# BSPD_5_11_27.net
KiCad netlist of a schematic drawn in EAGLE
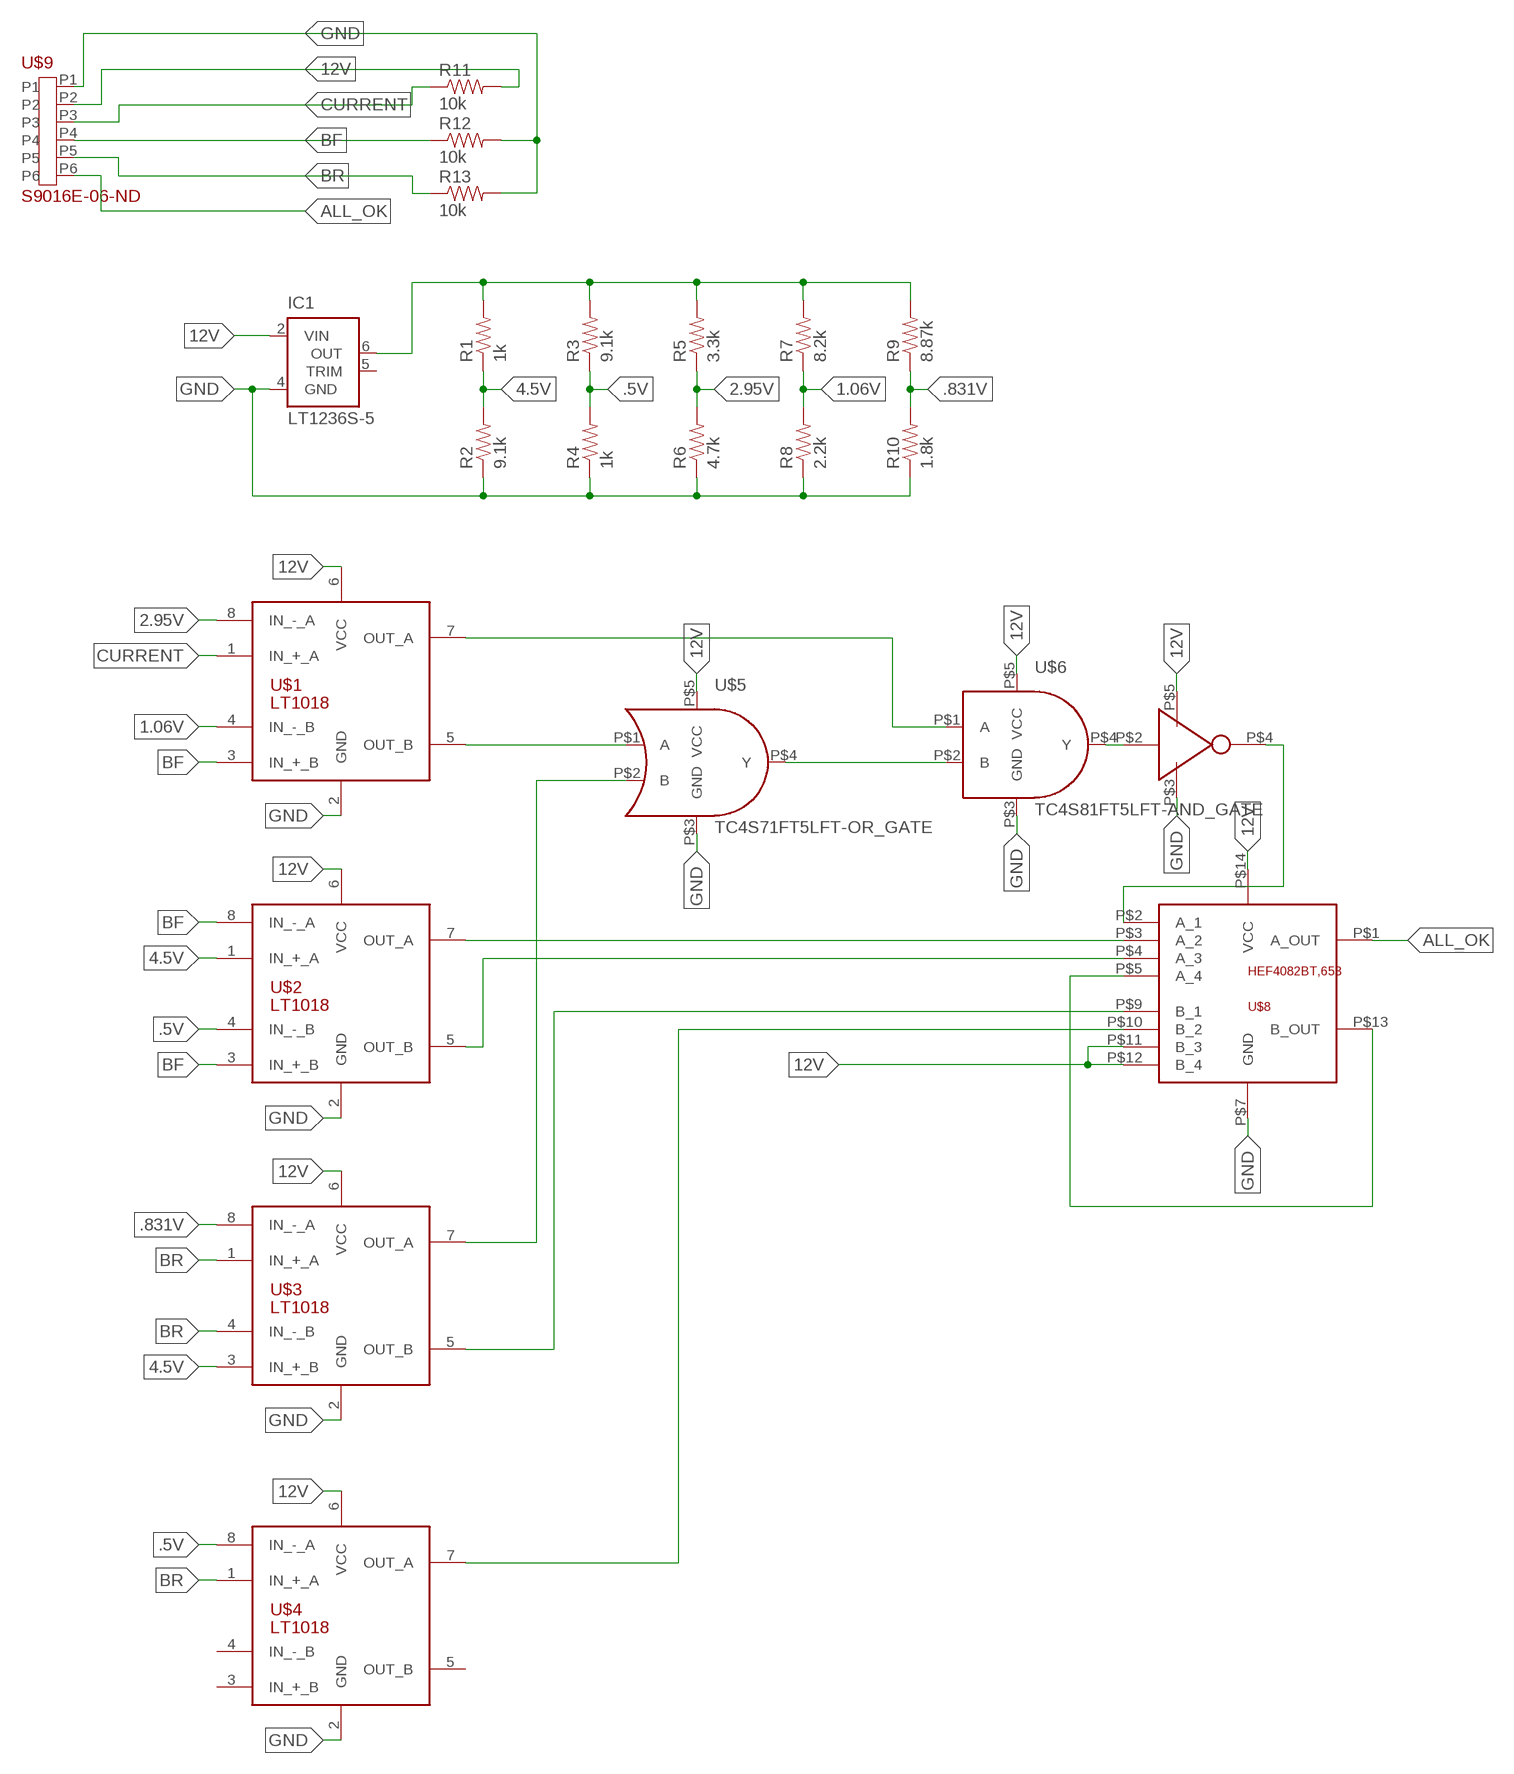
[diagram p0: schematic, sheet 1]

(export (version "E")
  (design (tool "Eeschema 10.0.6"))
  (components
    (comp (ref "IC1")
      (value "LT1236S-5")
      (footprint "eagle-import:SOIC8")
      (libsource (lib "eagle-import") (part "LT1236?S-5"))
    )
    (comp (ref "R1")
      (value "1k")
      (footprint "eagle-import:0603-RES")
      (libsource (lib "eagle-import") (part "RESISTOR0603"))
    )
    (comp (ref "R2")
      (value "9.1k")
      (footprint "eagle-import:0603-RES")
      (libsource (lib "eagle-import") (part "RESISTOR0603"))
    )
    (comp (ref "R3")
      (value "9.1k")
      (footprint "eagle-import:0603-RES")
      (libsource (lib "eagle-import") (part "RESISTOR0603"))
    )
    (comp (ref "R4")
      (value "1k")
      (footprint "eagle-import:0603-RES")
      (libsource (lib "eagle-import") (part "RESISTOR0603"))
    )
    (comp (ref "R5")
      (value "3.3k")
      (footprint "eagle-import:0603-RES")
      (libsource (lib "eagle-import") (part "RESISTOR0603"))
    )
    (comp (ref "R6")
      (value "4.7k")
      (footprint "eagle-import:0603-RES")
      (libsource (lib "eagle-import") (part "RESISTOR0603"))
    )
    (comp (ref "R7")
      (value "8.2k")
      (footprint "eagle-import:0603-RES")
      (libsource (lib "eagle-import") (part "RESISTOR0603"))
    )
    (comp (ref "R8")
      (value "2.2k")
      (footprint "eagle-import:0603-RES")
      (libsource (lib "eagle-import") (part "RESISTOR0603"))
    )
    (comp (ref "R9")
      (value "8.87k")
      (footprint "eagle-import:0603-RES")
      (libsource (lib "eagle-import") (part "RESISTOR0603"))
    )
    (comp (ref "R10")
      (value "1.8k")
      (footprint "eagle-import:0603-RES")
      (libsource (lib "eagle-import") (part "RESISTOR0603"))
    )
    (comp (ref "R11")
      (value "10k")
      (footprint "eagle-import:0603-RES")
      (libsource (lib "eagle-import") (part "RESISTOR0603"))
    )
    (comp (ref "R12")
      (value "10k")
      (footprint "eagle-import:0603-RES")
      (libsource (lib "eagle-import") (part "RESISTOR0603"))
    )
    (comp (ref "R13")
      (value "10k")
      (footprint "eagle-import:0603-RES")
      (libsource (lib "eagle-import") (part "RESISTOR0603"))
    )
    (comp (ref "U$1")
      (value "LT1018")
      (footprint "eagle-import:SOIC8")
      (libsource (lib "eagle-import") (part "LT1018"))
    )
    (comp (ref "U$2")
      (value "LT1018")
      (footprint "eagle-import:SOIC8")
      (libsource (lib "eagle-import") (part "LT1018"))
    )
    (comp (ref "U$3")
      (value "LT1018")
      (footprint "eagle-import:SOIC8")
      (libsource (lib "eagle-import") (part "LT1018"))
    )
    (comp (ref "U$4")
      (value "LT1018")
      (footprint "eagle-import:SOIC8")
      (libsource (lib "eagle-import") (part "LT1018"))
    )
    (comp (ref "U$5")
      (value "TC4S71FT5LFT-OR_GATE")
      (footprint "eagle-import:SSOP5-P-0.95")
      (libsource (lib "eagle-import") (part "TC4S71FT5LFT-OR_GATE"))
    )
    (comp (ref "U$6")
      (value "TC4S81FT5LFT-AND_GATE")
      (footprint "eagle-import:SSOP5-P-0.95")
      (libsource (lib "eagle-import") (part "TC4S81FT5LFT-AND_GATE"))
    )
    (comp (ref "U$7")
      (value "TC4S69F(TE85L,F)")
      (footprint "eagle-import:SSOP5-P-0.95")
      (libsource (lib "eagle-import") (part "TC4S69F(TE85L,F)"))
    )
    (comp (ref "U$8")
      (value "HEF4082BT,653")
      (footprint "eagle-import:NXP_14_SOIC")
      (libsource (lib "eagle-import") (part "HEF4082BT,653"))
    )
    (comp (ref "U$9")
      (value "S9016E-06-ND")
      (footprint "eagle-import:S9016E-05-ND")
      (libsource (lib "eagle-import") (part "S9016E-06-ND"))
    )
  )
  (nets
    (net (code "1") (name ".5V") (class "Default")
      (node (ref "R3") (pin "1") (pinfunction "1_1") (pintype "passive"))
      (node (ref "R4") (pin "2") (pinfunction "2_2") (pintype "passive"))
      (node (ref "U$2") (pin "4") (pinfunction "IN_-_B_4") (pintype "input"))
      (node (ref "U$4") (pin "8") (pinfunction "IN_-_A_8") (pintype "input"))
    )
    (net (code "2") (name ".831V") (class "Default")
      (node (ref "R10") (pin "2") (pinfunction "2_2") (pintype "passive"))
      (node (ref "R9") (pin "1") (pinfunction "1_1") (pintype "passive"))
      (node (ref "U$3") (pin "8") (pinfunction "IN_-_A_8") (pintype "input"))
    )
    (net (code "3") (name "1.06V") (class "Default")
      (node (ref "R7") (pin "1") (pinfunction "1_1") (pintype "passive"))
      (node (ref "R8") (pin "2") (pinfunction "2_2") (pintype "passive"))
      (node (ref "U$1") (pin "4") (pinfunction "IN_-_B_4") (pintype "input"))
    )
    (net (code "4") (name "2.95V") (class "Default")
      (node (ref "R5") (pin "1") (pinfunction "1_1") (pintype "passive"))
      (node (ref "R6") (pin "2") (pinfunction "2_2") (pintype "passive"))
      (node (ref "U$1") (pin "8") (pinfunction "IN_-_A_8") (pintype "input"))
    )
    (net (code "5") (name "4.5V") (class "Default")
      (node (ref "R1") (pin "1") (pinfunction "1_1") (pintype "passive"))
      (node (ref "R2") (pin "2") (pinfunction "2_2") (pintype "passive"))
      (node (ref "U$2") (pin "1") (pinfunction "IN_+_A_1") (pintype "input"))
      (node (ref "U$3") (pin "3") (pinfunction "IN_+_B_3") (pintype "input"))
    )
    (net (code "6") (name "12V") (class "Default")
      (node (ref "IC1") (pin "2") (pinfunction "VIN_2") (pintype "input"))
      (node (ref "R11") (pin "2") (pinfunction "2_2") (pintype "passive"))
      (node (ref "U$1") (pin "6") (pinfunction "VCC_6") (pintype "power_in"))
      (node (ref "U$2") (pin "6") (pinfunction "VCC_6") (pintype "power_in"))
      (node (ref "U$3") (pin "6") (pinfunction "VCC_6") (pintype "power_in"))
      (node (ref "U$4") (pin "6") (pinfunction "VCC_6") (pintype "power_in"))
      (node (ref "U$5") (pin "P$5") (pinfunction "VCC_P$5") (pintype "bidirectional"))
      (node (ref "U$6") (pin "P$5") (pinfunction "VCC_P$5") (pintype "bidirectional"))
      (node (ref "U$7") (pin "P$5") (pinfunction "VCC_P$5") (pintype "power_in"))
      (node (ref "U$8") (pin "P$11") (pinfunction "B_3_P$11") (pintype "open_collector"))
      (node (ref "U$8") (pin "P$12") (pinfunction "B_4_P$12") (pintype "open_collector"))
      (node (ref "U$8") (pin "P$14") (pinfunction "VCC_P$14") (pintype "power_in"))
      (node (ref "U$9") (pin "P2") (pinfunction "P2_P2") (pintype "bidirectional"))
    )
    (net (code "7") (name "ALL_OK") (class "Default")
      (node (ref "U$8") (pin "P$1") (pinfunction "A_OUT_P$1") (pintype "output"))
      (node (ref "U$9") (pin "P6") (pinfunction "P6_P6") (pintype "bidirectional"))
    )
    (net (code "8") (name "BF") (class "Default")
      (node (ref "R12") (pin "1") (pinfunction "1_1") (pintype "passive"))
      (node (ref "U$1") (pin "3") (pinfunction "IN_+_B_3") (pintype "input"))
      (node (ref "U$2") (pin "3") (pinfunction "IN_+_B_3") (pintype "input"))
      (node (ref "U$2") (pin "8") (pinfunction "IN_-_A_8") (pintype "input"))
      (node (ref "U$9") (pin "P4") (pinfunction "P4_P4") (pintype "bidirectional"))
    )
    (net (code "9") (name "BR") (class "Default")
      (node (ref "R13") (pin "1") (pinfunction "1_1") (pintype "passive"))
      (node (ref "U$3") (pin "1") (pinfunction "IN_+_A_1") (pintype "input"))
      (node (ref "U$3") (pin "4") (pinfunction "IN_-_B_4") (pintype "input"))
      (node (ref "U$4") (pin "1") (pinfunction "IN_+_A_1") (pintype "input"))
      (node (ref "U$9") (pin "P5") (pinfunction "P5_P5") (pintype "bidirectional"))
    )
    (net (code "10") (name "CURRENT") (class "Default")
      (node (ref "R11") (pin "1") (pinfunction "1_1") (pintype "passive"))
      (node (ref "U$1") (pin "1") (pinfunction "IN_+_A_1") (pintype "input"))
      (node (ref "U$9") (pin "P3") (pinfunction "P3_P3") (pintype "bidirectional"))
    )
    (net (code "11") (name "GND") (class "Default")
      (node (ref "IC1") (pin "4") (pinfunction "GND_4") (pintype "power_in"))
      (node (ref "R10") (pin "1") (pinfunction "1_1") (pintype "passive"))
      (node (ref "R12") (pin "2") (pinfunction "2_2") (pintype "passive"))
      (node (ref "R13") (pin "2") (pinfunction "2_2") (pintype "passive"))
      (node (ref "R2") (pin "1") (pinfunction "1_1") (pintype "passive"))
      (node (ref "R4") (pin "1") (pinfunction "1_1") (pintype "passive"))
      (node (ref "R6") (pin "1") (pinfunction "1_1") (pintype "passive"))
      (node (ref "R8") (pin "1") (pinfunction "1_1") (pintype "passive"))
      (node (ref "U$1") (pin "2") (pinfunction "GND_2") (pintype "power_in"))
      (node (ref "U$2") (pin "2") (pinfunction "GND_2") (pintype "power_in"))
      (node (ref "U$3") (pin "2") (pinfunction "GND_2") (pintype "power_in"))
      (node (ref "U$4") (pin "2") (pinfunction "GND_2") (pintype "power_in"))
      (node (ref "U$5") (pin "P$3") (pinfunction "GND_P$3") (pintype "bidirectional"))
      (node (ref "U$6") (pin "P$3") (pinfunction "GND_P$3") (pintype "bidirectional"))
      (node (ref "U$7") (pin "P$3") (pinfunction "GND_P$3") (pintype "power_in"))
      (node (ref "U$8") (pin "P$7") (pinfunction "GND_P$7") (pintype "power_in"))
      (node (ref "U$9") (pin "P1") (pinfunction "P1_P1") (pintype "bidirectional"))
    )
    (net (code "12") (name "Net-(IC1-OUT)") (class "Default")
      (node (ref "IC1") (pin "6") (pinfunction "OUT_6") (pintype "input"))
      (node (ref "R1") (pin "2") (pinfunction "2_2") (pintype "passive"))
      (node (ref "R3") (pin "2") (pinfunction "2_2") (pintype "passive"))
      (node (ref "R5") (pin "2") (pinfunction "2_2") (pintype "passive"))
      (node (ref "R7") (pin "2") (pinfunction "2_2") (pintype "passive"))
      (node (ref "R9") (pin "2") (pinfunction "2_2") (pintype "passive"))
    )
    (net (code "13") (name "Net-(U$1-OUT_A)") (class "Default")
      (node (ref "U$1") (pin "7") (pinfunction "OUT_A_7") (pintype "output"))
      (node (ref "U$6") (pin "P$1") (pinfunction "A_P$1") (pintype "bidirectional"))
    )
    (net (code "14") (name "Net-(U$1-OUT_B)") (class "Default")
      (node (ref "U$1") (pin "5") (pinfunction "OUT_B_5") (pintype "output"))
      (node (ref "U$5") (pin "P$1") (pinfunction "A_P$1") (pintype "bidirectional"))
    )
    (net (code "15") (name "Net-(U$2-OUT_A)") (class "Default")
      (node (ref "U$2") (pin "7") (pinfunction "OUT_A_7") (pintype "output"))
      (node (ref "U$8") (pin "P$3") (pinfunction "A_2_P$3") (pintype "open_collector"))
    )
    (net (code "16") (name "Net-(U$2-OUT_B)") (class "Default")
      (node (ref "U$2") (pin "5") (pinfunction "OUT_B_5") (pintype "output"))
      (node (ref "U$8") (pin "P$4") (pinfunction "A_3_P$4") (pintype "open_collector"))
    )
    (net (code "17") (name "Net-(U$3-OUT_A)") (class "Default")
      (node (ref "U$3") (pin "7") (pinfunction "OUT_A_7") (pintype "output"))
      (node (ref "U$5") (pin "P$2") (pinfunction "B_P$2") (pintype "bidirectional"))
    )
    (net (code "18") (name "Net-(U$3-OUT_B)") (class "Default")
      (node (ref "U$3") (pin "5") (pinfunction "OUT_B_5") (pintype "output"))
      (node (ref "U$8") (pin "P$9") (pinfunction "B_1_P$9") (pintype "open_collector"))
    )
    (net (code "19") (name "Net-(U$4-OUT_A)") (class "Default")
      (node (ref "U$4") (pin "7") (pinfunction "OUT_A_7") (pintype "output"))
      (node (ref "U$8") (pin "P$10") (pinfunction "B_2_P$10") (pintype "open_collector"))
    )
    (net (code "20") (name "Net-(U$5-Y)") (class "Default")
      (node (ref "U$5") (pin "P$4") (pinfunction "Y_P$4") (pintype "bidirectional"))
      (node (ref "U$6") (pin "P$2") (pinfunction "B_P$2") (pintype "bidirectional"))
    )
    (net (code "21") (name "Net-(U$6-Y)") (class "Default")
      (node (ref "U$6") (pin "P$4") (pinfunction "Y_P$4") (pintype "bidirectional"))
      (node (ref "U$7") (pin "P$2") (pinfunction "IN_P$2") (pintype "input"))
    )
    (net (code "22") (name "Net-(U$7-OUT)") (class "Default")
      (node (ref "U$7") (pin "P$4") (pinfunction "OUT_P$4") (pintype "output"))
      (node (ref "U$8") (pin "P$2") (pinfunction "A_1_P$2") (pintype "open_collector"))
    )
    (net (code "23") (name "Net-(U$8-A_4)") (class "Default")
      (node (ref "U$8") (pin "P$13") (pinfunction "B_OUT_P$13") (pintype "output"))
      (node (ref "U$8") (pin "P$5") (pinfunction "A_4_P$5") (pintype "open_collector"))
    )
    (net (code "24") (name "unconnected-(IC1-TRIM-Pad5)") (class "Default")
      (node (ref "IC1") (pin "5") (pinfunction "TRIM_5") (pintype "passive"))
    )
    (net (code "25") (name "unconnected-(U$4-IN_+_B-Pad3)") (class "Default")
      (node (ref "U$4") (pin "3") (pinfunction "IN_+_B_3") (pintype "input"))
    )
    (net (code "26") (name "unconnected-(U$4-IN_-_B-Pad4)") (class "Default")
      (node (ref "U$4") (pin "4") (pinfunction "IN_-_B_4") (pintype "input"))
    )
    (net (code "27") (name "unconnected-(U$4-OUT_B-Pad5)") (class "Default")
      (node (ref "U$4") (pin "5") (pinfunction "OUT_B_5") (pintype "output"))
    )
  )
)
